# Hall.net
KiCad netlist of a schematic drawn in Altium Designer
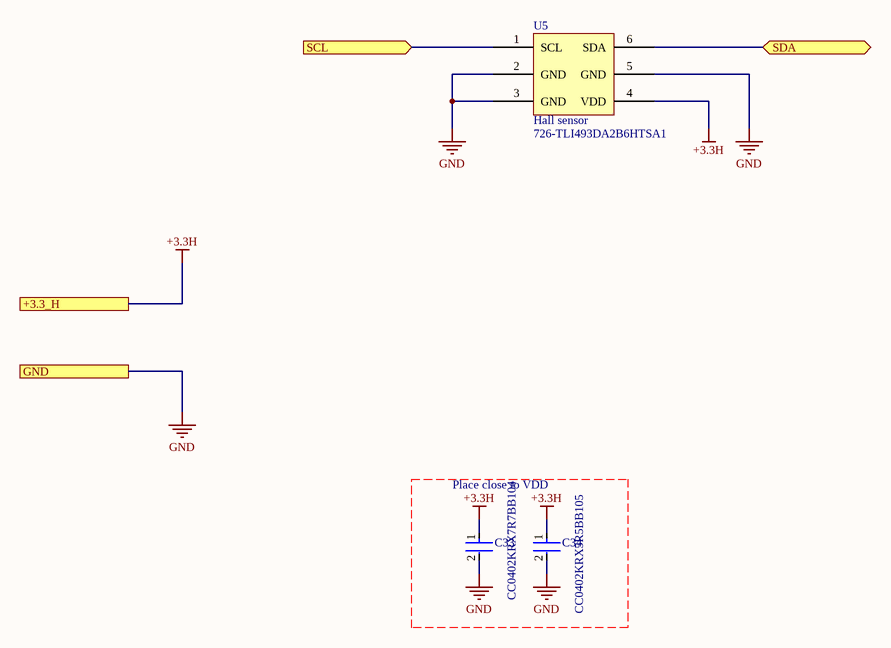
[diagram p0: Hall.SchDoc]

(export (version "E")
  (design (tool "Eeschema 10.0.6"))
  (components
    (comp (ref "C33")
      (value "CC0402KRX7R7BB104")
      (footprint "FP-CC0402-MFG")
      (description "CAP CER 0.1UF 16V X7R 0402")
      (fields (field (name "MANUFACTURER") "YAGEO") (field (name "TOLERANCE") "0.1"))
      (libsource (lib "Altium Content Vault") (part "11868f565c42a9108669ba33697ecf6"))
    )
    (comp (ref "C34")
      (value "CC0402KRX5R5BB105")
      (footprint "FP-CC0402-MFG")
      (description "CAP CER 1UF 6.3V X5R 0402")
      (fields
        (field (name "MANUFACTURER") "YAGEO")
        (field (name "OCTOPART") "https://octopart.com/cc0402krx5r5bb105-yageo-42244618")
      )
      (libsource (lib "Altium Content Vault") (part "11868f565c42a9108669ba33697ecf6"))
    )
    (comp (ref "U5")
      (value "Hall sensor")
      (footprint "TSOP6")
      (fields (field (name "SUPPLIER PART NUMBER 1") "726-TLI493DA2B6HTSA1"))
      (libsource (lib "Coin_lib") (part "TLI493DA2B6HTSA1"))
    )
  )
  (nets
    (net (code "1") (name "+3.3H") (class "Default")
      (node (ref "C33") (pin "1") (pinfunction "1_1") (pintype "passive"))
      (node (ref "C34") (pin "1") (pinfunction "1_1") (pintype "passive"))
      (node (ref "U5") (pin "4") (pinfunction "VDD_4") (pintype "passive"))
    )
    (net (code "2") (name "/SCL") (class "Default")
      (node (ref "U5") (pin "1") (pinfunction "SCL_1") (pintype "passive"))
    )
    (net (code "3") (name "/SDA") (class "Default")
      (node (ref "U5") (pin "6") (pinfunction "SDA_6") (pintype "passive"))
    )
    (net (code "4") (name "GND") (class "Default")
      (node (ref "C33") (pin "2") (pinfunction "2_2") (pintype "passive"))
      (node (ref "C34") (pin "2") (pinfunction "2_2") (pintype "passive"))
      (node (ref "U5") (pin "2") (pinfunction "GND_2") (pintype "passive"))
      (node (ref "U5") (pin "3") (pinfunction "GND_3") (pintype "passive"))
      (node (ref "U5") (pin "5") (pinfunction "GND_5") (pintype "passive"))
    )
  )
)
